# Connectors.net
KiCad netlist of a schematic drawn in Altium Designer
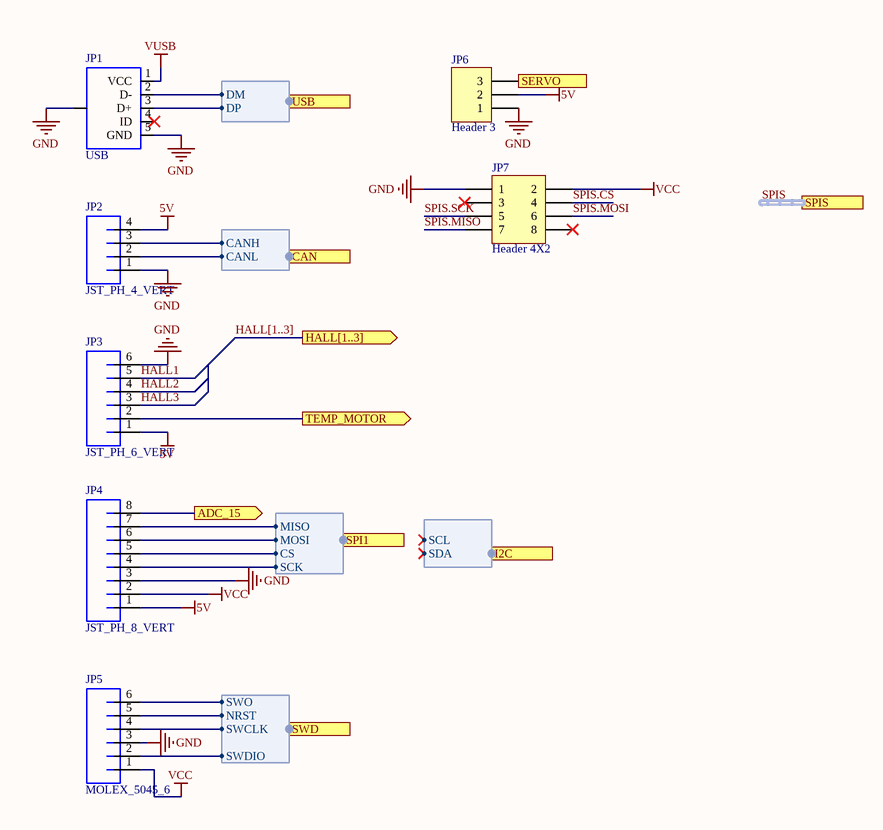
[diagram p0: Connectors.SchDoc]

(export (version "E")
  (design (tool "Eeschema 10.0.6"))
  (components
    (comp (ref "JP1")
      (value "USB")
      (footprint "USB-MICROB_HORZ")
      (fields (field (name "PARTNUMBER") "10118192-0001LF") (field (name "MANUFACTURER") "Amphenol FCI"))
      (libsource (lib "Connectors") (part "USB_MICROB_SMT"))
    )
    (comp (ref "JP2")
      (value "JST_PH_4_VERT")
      (footprint "JST-PH-4-PTH-VERT")
      (fields
        (field (name "PARTNUMBER") "B4B-PH-K-S(LF)(SN)")
        (field (name "MANUFACTURER") "JST Sales America Inc.")
      )
      (libsource (lib "Connectors") (part "JST_PH_4_VERT"))
    )
    (comp (ref "JP3")
      (value "JST_PH_6_VERT")
      (footprint "JST-PH-6-PTH-VERT")
      (fields
        (field (name "PARTNUMBER") "B6B-PH-K-S(LF)(SN)")
        (field (name "MANUFACTURER") "JST Sales America Inc.")
      )
      (libsource (lib "Connectors") (part "JST_PH_6_VERT"))
    )
    (comp (ref "JP4")
      (value "JST_PH_8_VERT")
      (footprint "JST-PH-8-PTH-VERT")
      (fields
        (field (name "MANUFACTURER") "JST Sales America Inc.")
        (field (name "PARTNUMBER") "B8B-PH-K-S(LF)(SN)")
      )
      (libsource (lib "Connectors") (part "JST_PH_8_VERT"))
    )
    (comp (ref "JP5")
      (value "MOLEX_5045_6")
      (footprint "MOLEX_5045_6")
      (fields
        (field (name "PARTNUMBER") "B6B-PH-K-S(LF)(SN)")
        (field (name "MANUFACTURER") "JST Sales America Inc.")
      )
      (libsource (lib "Connectors") (part "MOLEX_5045_6"))
    )
    (comp (ref "JP6")
      (value "Header 3")
      (footprint "HDR1X3")
      (description "Header, 3-Pin")
      (fields (field (name "PUBLISHER") "Altium Limited"))
      (libsource (lib "Miscellaneous Connectors") (part "Header 3"))
    )
    (comp (ref "JP7")
      (value "Header 4X2")
      (footprint "HDR2X4")
      (description "Header, 4-Pin, Dual row")
      (fields (field (name "PUBLISHER") "Altium Limited"))
      (libsource (lib "Miscellaneous Connectors") (part "Header 4X2"))
    )
  )
  (nets
    (net (code "8") (name "/ADC_15") (class "Default")
      (node (ref "JP4") (pin "8") (pinfunction "8_8") (pintype "passive"))
    )
    (net (code "9") (name "/CANH") (class "Default")
      (node (ref "JP2") (pin "3") (pinfunction "3_3") (pintype "passive"))
    )
    (net (code "10") (name "/CANL") (class "Default")
      (node (ref "JP2") (pin "2") (pinfunction "2_2") (pintype "passive"))
    )
    (net (code "11") (name "/CS") (class "Default")
      (node (ref "JP4") (pin "5") (pinfunction "5_5") (pintype "passive"))
    )
    (net (code "12") (name "/DM") (class "Default")
      (node (ref "JP1") (pin "2") (pinfunction "D-_2") (pintype "passive"))
    )
    (net (code "13") (name "/DP") (class "Default")
      (node (ref "JP1") (pin "3") (pinfunction "D+_3") (pintype "passive"))
    )
    (net (code "14") (name "/HALL1") (class "Default")
      (node (ref "JP3") (pin "5") (pinfunction "5_5") (pintype "passive"))
    )
    (net (code "15") (name "/HALL2") (class "Default")
      (node (ref "JP3") (pin "4") (pinfunction "4_4") (pintype "passive"))
    )
    (net (code "16") (name "/HALL3") (class "Default")
      (node (ref "JP3") (pin "3") (pinfunction "3_3") (pintype "passive"))
    )
    (net (code "18") (name "/MISO") (class "Default")
      (node (ref "JP4") (pin "7") (pinfunction "7_7") (pintype "passive"))
    )
    (net (code "19") (name "/MOSI") (class "Default")
      (node (ref "JP4") (pin "6") (pinfunction "6_6") (pintype "passive"))
    )
    (net (code "20") (name "/NRST") (class "Default")
      (node (ref "JP5") (pin "5") (pinfunction "5_5") (pintype "passive"))
    )
    (net (code "21") (name "/SCK") (class "Default")
      (node (ref "JP4") (pin "4") (pinfunction "4_4") (pintype "passive"))
    )
    (net (code "22") (name "/SERVO") (class "Default")
      (node (ref "JP6") (pin "3") (pinfunction "3_3") (pintype "passive"))
    )
    (net (code "23") (name "/SPIS.CS") (class "Default")
      (node (ref "JP7") (pin "4") (pinfunction "4_4") (pintype "passive"))
    )
    (net (code "24") (name "/SPIS.MISO") (class "Default")
      (node (ref "JP7") (pin "7") (pinfunction "7_7") (pintype "passive"))
    )
    (net (code "25") (name "/SPIS.MOSI") (class "Default")
      (node (ref "JP7") (pin "6") (pinfunction "6_6") (pintype "passive"))
    )
    (net (code "26") (name "/SPIS.SCK") (class "Default")
      (node (ref "JP7") (pin "5") (pinfunction "5_5") (pintype "passive"))
    )
    (net (code "27") (name "/SWCLK") (class "Default")
      (node (ref "JP5") (pin "4") (pinfunction "4_4") (pintype "passive"))
    )
    (net (code "28") (name "/SWDIO") (class "Default")
      (node (ref "JP5") (pin "2") (pinfunction "2_2") (pintype "passive"))
    )
    (net (code "29") (name "/SWO") (class "Default")
      (node (ref "JP5") (pin "6") (pinfunction "6_6") (pintype "passive"))
    )
    (net (code "30") (name "/TEMP_MOTOR") (class "Default")
      (node (ref "JP3") (pin "2") (pinfunction "2_2") (pintype "passive"))
    )
    (net (code "37") (name "5V") (class "Default")
      (node (ref "JP2") (pin "4") (pinfunction "4_4") (pintype "passive"))
      (node (ref "JP3") (pin "1") (pinfunction "1_1") (pintype "passive"))
      (node (ref "JP4") (pin "1") (pinfunction "1_1") (pintype "passive"))
      (node (ref "JP6") (pin "2") (pinfunction "2_2") (pintype "passive"))
    )
    (net (code "38") (name "GND") (class "Default")
      (node (ref "JP1") (pin "5") (pinfunction "GND_5") (pintype "passive"))
      (node (ref "JP1") (pin "6") (pinfunction "SHIELD_6") (pintype "passive"))
      (node (ref "JP2") (pin "1") (pinfunction "1_1") (pintype "passive"))
      (node (ref "JP3") (pin "6") (pinfunction "6_6") (pintype "passive"))
      (node (ref "JP4") (pin "3") (pinfunction "3_3") (pintype "passive"))
      (node (ref "JP5") (pin "3") (pinfunction "3_3") (pintype "passive"))
      (node (ref "JP6") (pin "1") (pinfunction "1_1") (pintype "passive"))
      (node (ref "JP7") (pin "1") (pinfunction "1_1") (pintype "passive"))
    )
    (net (code "39") (name "VCC") (class "Default")
      (node (ref "JP4") (pin "2") (pinfunction "2_2") (pintype "passive"))
      (node (ref "JP5") (pin "1") (pinfunction "1_1") (pintype "passive"))
      (node (ref "JP7") (pin "2") (pinfunction "2_2") (pintype "passive"))
    )
    (net (code "40") (name "VUSB") (class "Default")
      (node (ref "JP1") (pin "1") (pinfunction "VCC_1") (pintype "passive"))
    )
    (net (code "41") (name "unconnected-(JP1-ID-Pad4)") (class "Default")
      (node (ref "JP1") (pin "4") (pinfunction "ID_4") (pintype "passive+no_connect"))
    )
    (net (code "42") (name "unconnected-(JP7-Pad3)") (class "Default")
      (node (ref "JP7") (pin "3") (pinfunction "3_3") (pintype "passive+no_connect"))
    )
    (net (code "43") (name "unconnected-(JP7-Pad8)") (class "Default")
      (node (ref "JP7") (pin "8") (pinfunction "8_8") (pintype "passive+no_connect"))
    )
  )
)
